# BTLNhung-schematic.net
KiCad netlist of a schematic drawn in Altium Designer
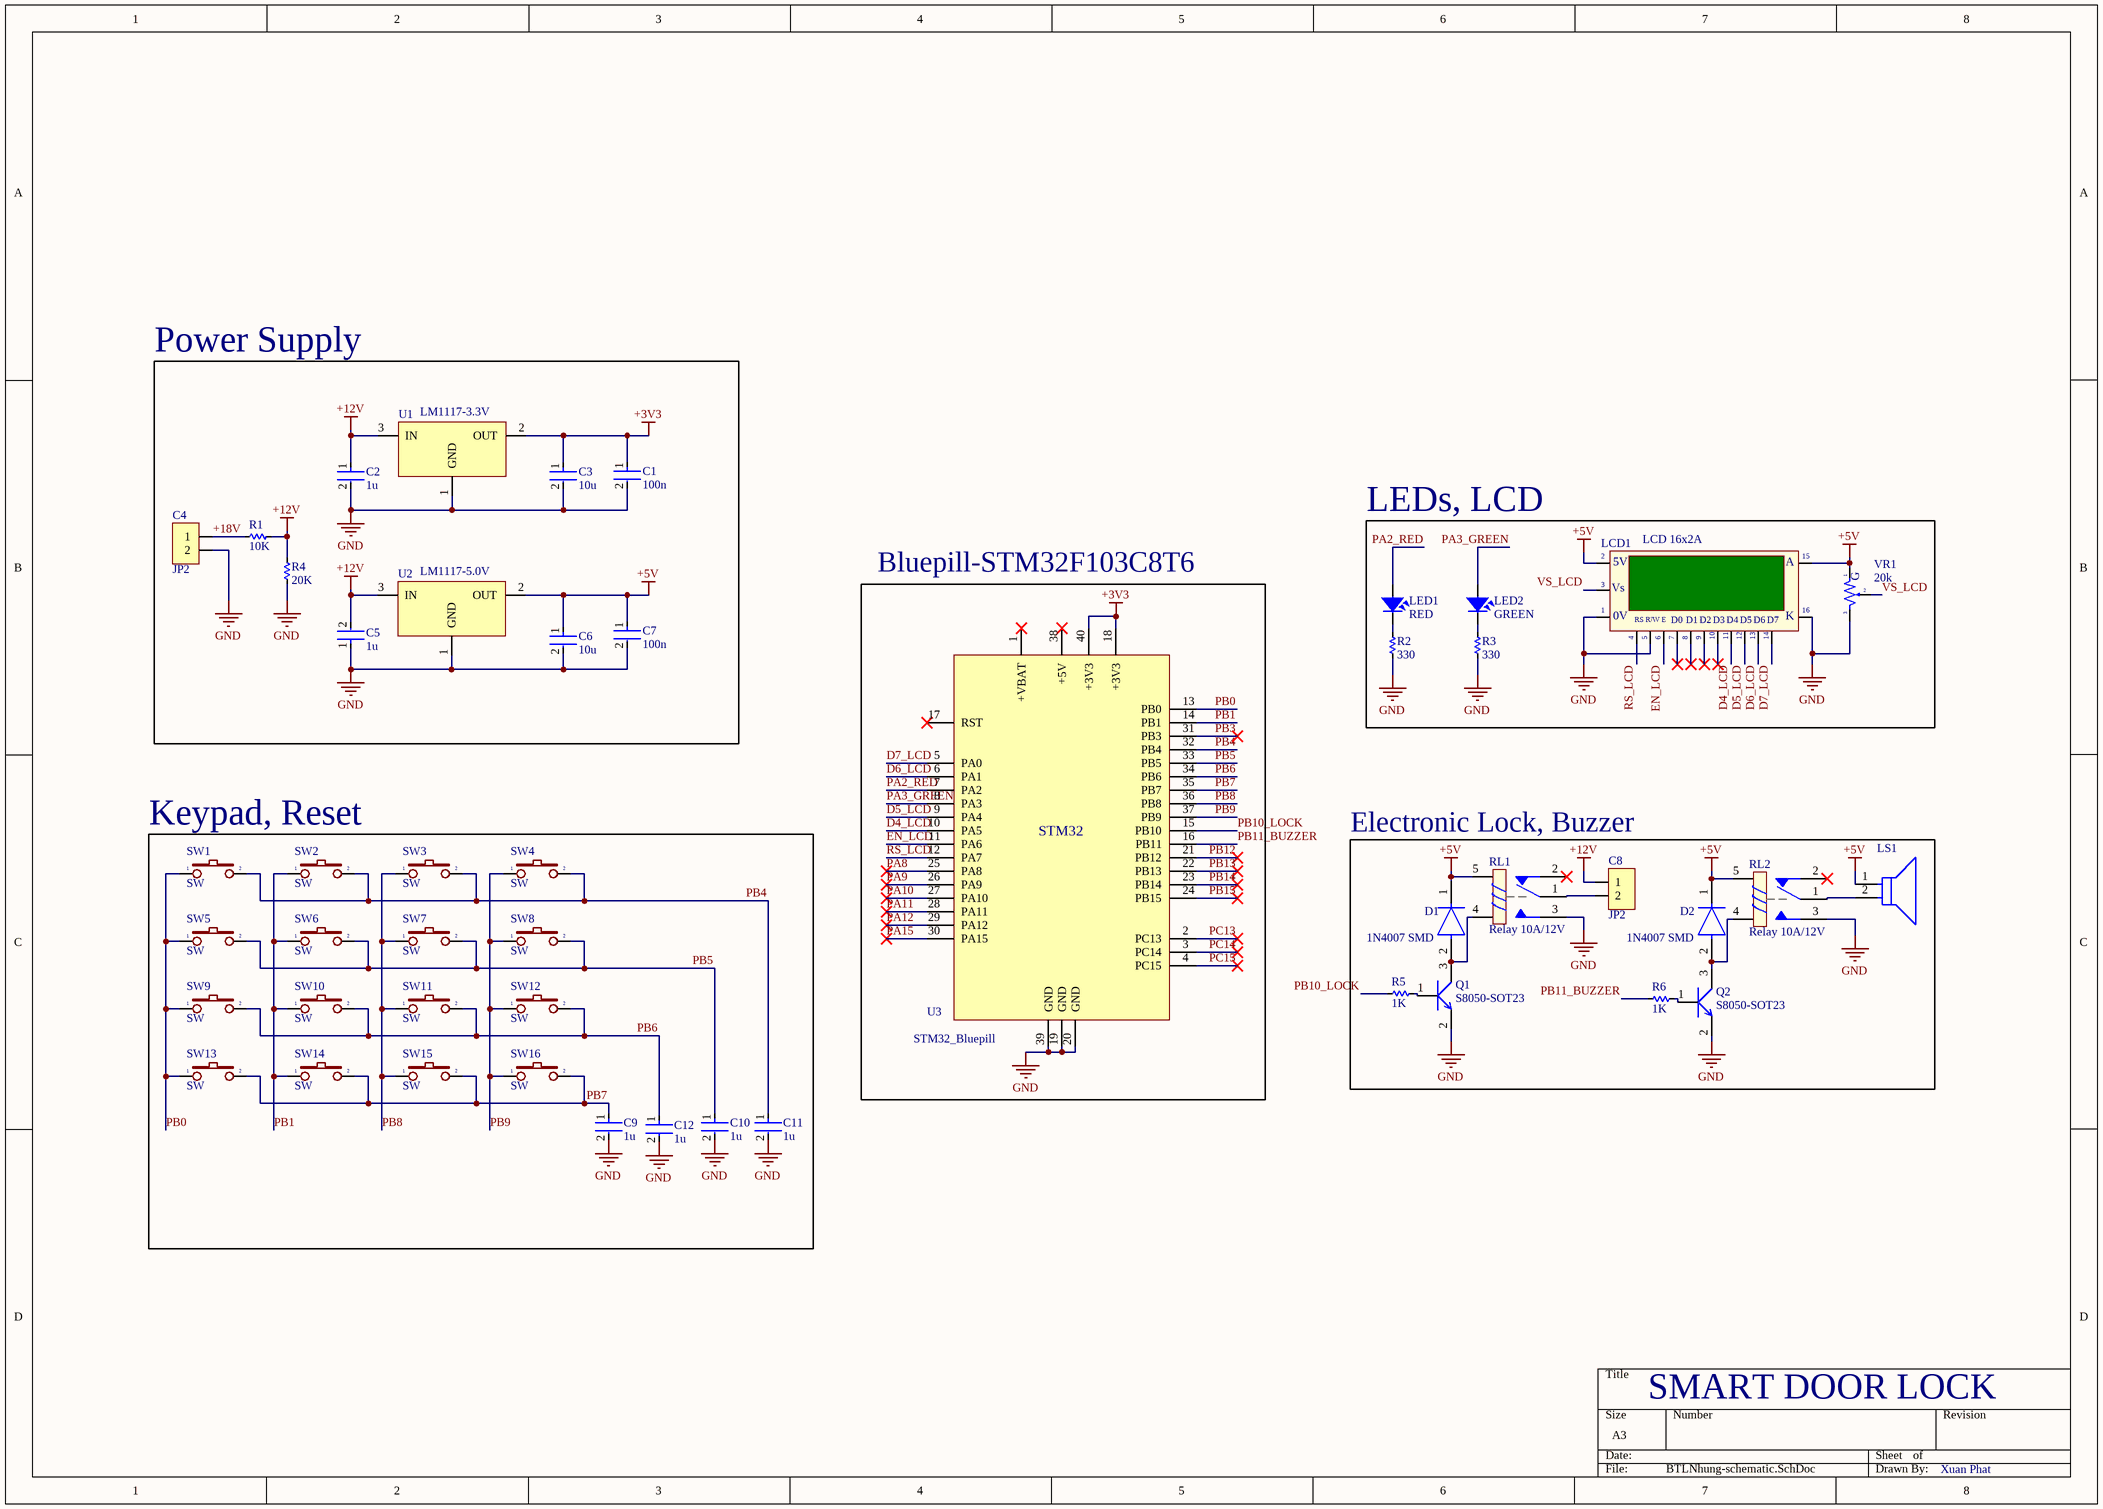
[diagram p0: BTLNhung-schematic.SchDoc]

(export (version "E")
  (design (tool "Eeschema 10.0.6"))
  (components
    (comp (ref "C1")
      (value "100n")
      (footprint "FP-GRM188-0_1-e0_2_0_55-IPC_A")
      (description "Chip Multilayer Ceramic Capacitors for General Purpose, 0603, 10uF, X5R, 15%, 20%, 6.3V")
      (fields (field (name "VOLTAGE") "6.3V") (field (name "TOLERANCE") "20%"))
      (libsource (lib "Altium Content Vault") (part "02cd4be3c70576c341d710602a673aa"))
    )
    (comp (ref "C2")
      (value "1u")
      (footprint "FP-GRM188-0_1-e0_2_0_55-IPC_A")
      (description "Chip Multilayer Ceramic Capacitors for General Purpose, 0603, 10uF, X5R, 15%, 20%, 6.3V")
      (fields (field (name "VOLTAGE") "6.3V") (field (name "TOLERANCE") "20%"))
      (libsource (lib "Altium Content Vault") (part "02cd4be3c70576c341d710602a673aa"))
    )
    (comp (ref "C3")
      (value "10u")
      (footprint "FP-GRM188-0_1-e0_2_0_55-IPC_A")
      (description "Chip Multilayer Ceramic Capacitors for General Purpose, 0603, 10uF, X5R, 15%, 20%, 6.3V")
      (fields (field (name "VOLTAGE") "6.3V") (field (name "TOLERANCE") "20%"))
      (libsource (lib "Altium Content Vault") (part "02cd4be3c70576c341d710602a673aa"))
    )
    (comp (ref "C4")
      (value "JP2")
      (footprint "JP2-D1C")
      (description "WR-PHD 2.54 mm Angled Socket Header")
      (fields
        (field (name "MANUFACTURER") "Würth Elektronik eiSos GmbH")
        (field (name "PARTNO") "613002143121")
        (field (name "CREATED BY") "Karrer Zheng")
      )
      (libsource (lib "") (part "JP2_1"))
    )
    (comp (ref "C5")
      (value "1u")
      (footprint "FP-GRM188-0_1-e0_2_0_55-IPC_A")
      (description "Chip Multilayer Ceramic Capacitors for General Purpose, 0603, 10uF, X5R, 15%, 20%, 6.3V")
      (fields (field (name "VOLTAGE") "6.3V") (field (name "TOLERANCE") "20%"))
      (libsource (lib "Altium Content Vault") (part "02cd4be3c70576c341d710602a673aa"))
    )
    (comp (ref "C6")
      (value "10u")
      (footprint "FP-GRM188-0_1-e0_2_0_55-IPC_A")
      (description "Chip Multilayer Ceramic Capacitors for General Purpose, 0603, 10uF, X5R, 15%, 20%, 6.3V")
      (fields (field (name "VOLTAGE") "6.3V") (field (name "TOLERANCE") "20%"))
      (libsource (lib "Altium Content Vault") (part "02cd4be3c70576c341d710602a673aa"))
    )
    (comp (ref "C7")
      (value "100n")
      (footprint "FP-GRM188-0_1-e0_2_0_55-IPC_A")
      (description "Chip Multilayer Ceramic Capacitors for General Purpose, 0603, 10uF, X5R, 15%, 20%, 6.3V")
      (fields (field (name "VOLTAGE") "6.3V") (field (name "TOLERANCE") "20%"))
      (libsource (lib "Altium Content Vault") (part "02cd4be3c70576c341d710602a673aa"))
    )
    (comp (ref "C8")
      (value "JP2")
      (footprint "JP2-D1C")
      (description "WR-PHD 2.54 mm Angled Socket Header")
      (fields
        (field (name "MANUFACTURER") "Würth Elektronik eiSos GmbH")
        (field (name "PARTNO") "613002143121")
        (field (name "CREATED BY") "Karrer Zheng")
      )
      (libsource (lib "Library") (part "JP2"))
    )
    (comp (ref "C9")
      (value "1u")
      (footprint "FP-GRM188-0_1-e0_2_0_55-IPC_A")
      (description "Chip Multilayer Ceramic Capacitors for General Purpose, 0603, 10uF, X5R, 15%, 20%, 6.3V")
      (fields (field (name "VOLTAGE") "6.3V") (field (name "TOLERANCE") "20%"))
      (libsource (lib "Altium Content Vault") (part "02cd4be3c70576c341d710602a673aa"))
    )
    (comp (ref "C10")
      (value "1u")
      (footprint "FP-GRM188-0_1-e0_2_0_55-IPC_A")
      (description "Chip Multilayer Ceramic Capacitors for General Purpose, 0603, 10uF, X5R, 15%, 20%, 6.3V")
      (fields (field (name "VOLTAGE") "6.3V") (field (name "TOLERANCE") "20%"))
      (libsource (lib "Altium Content Vault") (part "02cd4be3c70576c341d710602a673aa"))
    )
    (comp (ref "C11")
      (value "1u")
      (footprint "FP-GRM188-0_1-e0_2_0_55-IPC_A")
      (description "Chip Multilayer Ceramic Capacitors for General Purpose, 0603, 10uF, X5R, 15%, 20%, 6.3V")
      (fields (field (name "VOLTAGE") "6.3V") (field (name "TOLERANCE") "20%"))
      (libsource (lib "Altium Content Vault") (part "02cd4be3c70576c341d710602a673aa"))
    )
    (comp (ref "C12")
      (value "1u")
      (footprint "FP-GRM188-0_1-e0_2_0_55-IPC_A")
      (description "Chip Multilayer Ceramic Capacitors for General Purpose, 0603, 10uF, X5R, 15%, 20%, 6.3V")
      (fields (field (name "VOLTAGE") "6.3V") (field (name "TOLERANCE") "20%"))
      (libsource (lib "Altium Content Vault") (part "02cd4be3c70576c341d710602a673aa"))
    )
    (comp (ref "D1")
      (value "1N4007 SMD")
      (footprint "FP-1N4007_SMD-IPC_C")
      (description "Rectifier, 1Kv, 1A, Do-214Ac Rohs Compliant: Yes")
      (libsource (lib "Altium Content Vault") (part "d7152d700b627762746794eb795d46e"))
    )
    (comp (ref "D2")
      (value "1N4007 SMD")
      (footprint "FP-1N4007_SMD-IPC_C")
      (description "Rectifier, 1Kv, 1A, Do-214Ac Rohs Compliant: Yes")
      (libsource (lib "Altium Content Vault") (part "d7152d700b627762746794eb795d46e"))
    )
    (comp (ref "LCD1")
      (value "LCD 16x2A")
      (footprint "LCD16X2")
      (description "LCD dipslay 16 char, 2 line")
      (libsource (lib "Library") (part "LCD16x2A"))
    )
    (comp (ref "LED1") (value "RED") (footprint "LED-0805-Red") (libsource (lib "Library") (part "LED SMD")))
    (comp (ref "LED2")
      (value "GREEN")
      (footprint "LED-0805-Green")
      (libsource (lib "Library") (part "LED SMD"))
    )
    (comp (ref "LS1")
      (value "AT-1224-TWT-5V-2-R")
      (footprint "FP-AT-1224-TWT-5V-2-R-MFG")
      (description "BUZZER MAGNETIC 5V 12MM TH")
      (libsource (lib "Altium Content Vault") (part "1973c4b650225fd2ddacaff6b763965"))
    )
    (comp (ref "Q1")
      (value "S8050-SOT23")
      (footprint "SOT95P240X115-3N")
      (description "S8050 J3Y Transistor NPN 25V 0.5A 3 Pins SOT-23")
      (libsource (lib "S8050-SOT23") (part "S8050-SOT23"))
    )
    (comp (ref "Q2")
      (value "S8050-SOT23")
      (footprint "SOT95P240X115-3N")
      (description "S8050 J3Y Transistor NPN 25V 0.5A 3 Pins SOT-23")
      (libsource (lib "S8050-SOT23") (part "S8050-SOT23"))
    )
    (comp (ref "R1")
      (value "10K")
      (footprint "RES-SMD-0805")
      (description "Resistor")
      (fields
        (field (name "MANUFACTURER") "Generic Components")
        (field (name "PUBLISHER") "Altium Hobart Technology Centre")
      )
      (libsource (lib "Library") (part "Res-SMD"))
    )
    (comp (ref "R2")
      (value "330")
      (footprint "RES-SMD-0805")
      (description "Resistor")
      (fields
        (field (name "MANUFACTURER") "Generic Components")
        (field (name "PUBLISHER") "Altium Hobart Technology Centre")
      )
      (libsource (lib "Library") (part "Res-SMD"))
    )
    (comp (ref "R3")
      (value "330")
      (footprint "RES-SMD-0805")
      (description "Resistor")
      (fields
        (field (name "MANUFACTURER") "Generic Components")
        (field (name "PUBLISHER") "Altium Hobart Technology Centre")
      )
      (libsource (lib "Library") (part "Res-SMD"))
    )
    (comp (ref "R4")
      (value "20K")
      (footprint "RES-SMD-0805")
      (description "Resistor")
      (fields
        (field (name "MANUFACTURER") "Generic Components")
        (field (name "PUBLISHER") "Altium Hobart Technology Centre")
      )
      (libsource (lib "Library") (part "Res-SMD"))
    )
    (comp (ref "R5")
      (value "1K")
      (footprint "RES-SMD-0805")
      (description "Resistor")
      (fields
        (field (name "MANUFACTURER") "Generic Components")
        (field (name "PUBLISHER") "Altium Hobart Technology Centre")
      )
      (libsource (lib "Library") (part "Res-SMD"))
    )
    (comp (ref "R6")
      (value "1K")
      (footprint "RES-SMD-0805")
      (description "Resistor")
      (fields
        (field (name "MANUFACTURER") "Generic Components")
        (field (name "PUBLISHER") "Altium Hobart Technology Centre")
      )
      (libsource (lib "Library") (part "Res-SMD"))
    )
    (comp (ref "RL1")
      (value "Relay 10A/12V")
      (footprint "Relay - SRA-05VDC-CL")
      (description "Relay SPDT,10A - 12VDC 5 Pin")
      (libsource (lib "Library") (part "Relay 5"))
    )
    (comp (ref "RL2")
      (value "Relay 10A/12V")
      (footprint "Relay - SRA-05VDC-CL")
      (description "Relay SPDT,10A - 12VDC 5 Pin")
      (libsource (lib "Library") (part "Relay 5"))
    )
    (comp (ref "SW1")
      (value "SW")
      (footprint "SW1-DIP-12x12x8-Black")
      (description "Switch button 2 pin")
      (libsource (lib "Library") (part "SW2"))
    )
    (comp (ref "SW2")
      (value "SW")
      (footprint "SW1-DIP-12x12x8-Black")
      (description "Switch button 2 pin")
      (libsource (lib "Library") (part "SW2"))
    )
    (comp (ref "SW3")
      (value "SW")
      (footprint "SW1-DIP-12x12x8-Black")
      (description "Switch button 2 pin")
      (libsource (lib "Library") (part "SW2"))
    )
    (comp (ref "SW4")
      (value "SW")
      (footprint "SW1-DIP-12x12x8-Black")
      (description "Switch button 2 pin")
      (libsource (lib "Library") (part "SW2"))
    )
    (comp (ref "SW5")
      (value "SW")
      (footprint "SW1-DIP-12x12x8-Black")
      (description "Switch button 2 pin")
      (libsource (lib "Library") (part "SW2"))
    )
    (comp (ref "SW6")
      (value "SW")
      (footprint "SW1-DIP-12x12x8-Black")
      (description "Switch button 2 pin")
      (libsource (lib "Library") (part "SW2"))
    )
    (comp (ref "SW7")
      (value "SW")
      (footprint "SW1-DIP-12x12x8-Black")
      (description "Switch button 2 pin")
      (libsource (lib "Library") (part "SW2"))
    )
    (comp (ref "SW8")
      (value "SW")
      (footprint "SW1-DIP-12x12x8-Black")
      (description "Switch button 2 pin")
      (libsource (lib "Library") (part "SW2"))
    )
    (comp (ref "SW9")
      (value "SW")
      (footprint "SW1-DIP-12x12x8-Black")
      (description "Switch button 2 pin")
      (libsource (lib "Library") (part "SW2"))
    )
    (comp (ref "SW10")
      (value "SW")
      (footprint "SW1-DIP-12x12x8-Black")
      (description "Switch button 2 pin")
      (libsource (lib "Library") (part "SW2"))
    )
    (comp (ref "SW11")
      (value "SW")
      (footprint "SW1-DIP-12x12x8-Black")
      (description "Switch button 2 pin")
      (libsource (lib "Library") (part "SW2"))
    )
    (comp (ref "SW12")
      (value "SW")
      (footprint "SW1-DIP-12x12x8-Black")
      (description "Switch button 2 pin")
      (libsource (lib "Library") (part "SW2"))
    )
    (comp (ref "SW13")
      (value "SW")
      (footprint "SW1-DIP-12x12x8-Black")
      (description "Switch button 2 pin")
      (libsource (lib "Library") (part "SW2"))
    )
    (comp (ref "SW14")
      (value "SW")
      (footprint "SW1-DIP-12x12x8-Black")
      (description "Switch button 2 pin")
      (libsource (lib "Library") (part "SW2"))
    )
    (comp (ref "SW15")
      (value "SW")
      (footprint "SW1-DIP-12x12x8-Black")
      (description "Switch button 2 pin")
      (libsource (lib "Library") (part "SW2"))
    )
    (comp (ref "SW16")
      (value "SW")
      (footprint "SW1-DIP-12x12x8-Black")
      (description "Switch button 2 pin")
      (libsource (lib "Library") (part "SW2"))
    )
    (comp (ref "U1")
      (value "LM1117-3.3V")
      (footprint "SOT223")
      (description "800mA Low-Dropout Linear Regulator")
      (fields (field (name "CREATOR") "Nguyen Ba Bien"))
      (libsource (lib "Library") (part "LM1117"))
    )
    (comp (ref "U2")
      (value "LM1117-5.0V")
      (footprint "SOT223")
      (description "800mA Low-Dropout Linear Regulator")
      (fields (field (name "CREATOR") "Nguyen Ba Bien"))
      (libsource (lib "Library") (part "LM1117"))
    )
    (comp (ref "U3")
      (value "STM32_Bluepill")
      (footprint "STM32F103_BluePill")
      (libsource (lib "Library") (part "STM32_Bluepill"))
    )
    (comp (ref "VR1")
      (value "20k")
      (footprint "VR-S2")
      (description "Var Resistor")
      (libsource (lib "Library") (part "VR-S"))
    )
  )
  (nets
    (net (code "1") (name "+3V3") (class "Default")
      (node (ref "C1") (pin "1") (pinfunction "1_1") (pintype "passive"))
      (node (ref "C3") (pin "1") (pinfunction "1_1") (pintype "passive"))
      (node (ref "U1") (pin "2") (pinfunction "OUT_2") (pintype "passive"))
      (node (ref "U3") (pin "18") (pinfunction "+3V3_18") (pintype "passive"))
      (node (ref "U3") (pin "40") (pinfunction "+3V3_40") (pintype "passive"))
    )
    (net (code "2") (name "+5V") (class "Default")
      (node (ref "C6") (pin "1") (pinfunction "1_1") (pintype "passive"))
      (node (ref "C7") (pin "1") (pinfunction "1_1") (pintype "passive"))
      (node (ref "D1") (pin "1") (pinfunction "C_1") (pintype "passive"))
      (node (ref "D2") (pin "1") (pinfunction "C_1") (pintype "passive"))
      (node (ref "LCD1") (pin "15") (pinfunction "A_15") (pintype "passive"))
      (node (ref "LCD1") (pin "2") (pinfunction "VDD_2") (pintype "passive"))
      (node (ref "LS1") (pin "1") (pinfunction "C_1") (pintype "passive"))
      (node (ref "RL1") (pin "5") (pinfunction "5_5") (pintype "passive"))
      (node (ref "RL2") (pin "5") (pinfunction "5_5") (pintype "passive"))
      (node (ref "U2") (pin "2") (pinfunction "OUT_2") (pintype "passive"))
      (node (ref "VR1") (pin "1") (pinfunction "1_1") (pintype "passive"))
    )
    (net (code "3") (name "+12V") (class "Default")
      (node (ref "C2") (pin "1") (pinfunction "1_1") (pintype "passive"))
      (node (ref "C5") (pin "2") (pinfunction "2_2") (pintype "passive"))
      (node (ref "C8") (pin "1") (pinfunction "1_1") (pintype "passive"))
      (node (ref "R1") (pin "1") (pinfunction "1_1") (pintype "passive"))
      (node (ref "R4") (pin "1") (pinfunction "1_1") (pintype "passive"))
      (node (ref "U1") (pin "3") (pinfunction "IN_3") (pintype "passive"))
      (node (ref "U2") (pin "3") (pinfunction "IN_3") (pintype "passive"))
    )
    (net (code "4") (name "/+18V") (class "Default")
      (node (ref "C4") (pin "1") (pinfunction "1_1") (pintype "passive"))
      (node (ref "R1") (pin "2") (pinfunction "2_2") (pintype "passive"))
    )
    (net (code "5") (name "/D4_LCD") (class "Default")
      (node (ref "LCD1") (pin "11") (pinfunction "D4_11") (pintype "passive"))
      (node (ref "U3") (pin "10") (pinfunction "PA5_10") (pintype "passive"))
    )
    (net (code "6") (name "/D5_LCD") (class "Default")
      (node (ref "LCD1") (pin "12") (pinfunction "D5_12") (pintype "passive"))
      (node (ref "U3") (pin "9") (pinfunction "PA4_9") (pintype "passive"))
    )
    (net (code "7") (name "/D6_LCD") (class "Default")
      (node (ref "LCD1") (pin "13") (pinfunction "D6_13") (pintype "passive"))
      (node (ref "U3") (pin "6") (pinfunction "PA1_6") (pintype "passive"))
    )
    (net (code "8") (name "/D7_LCD") (class "Default")
      (node (ref "LCD1") (pin "14") (pinfunction "D7_14") (pintype "passive"))
      (node (ref "U3") (pin "5") (pinfunction "PA0_5") (pintype "passive"))
    )
    (net (code "9") (name "/EN_LCD") (class "Default")
      (node (ref "LCD1") (pin "6") (pinfunction "~{EN}_6") (pintype "passive"))
      (node (ref "U3") (pin "11") (pinfunction "PA6_11") (pintype "passive"))
    )
    (net (code "10") (name "/PA2_RED") (class "Default")
      (node (ref "LED1") (pin "1") (pinfunction "1_1") (pintype "passive"))
      (node (ref "U3") (pin "7") (pinfunction "PA2_7") (pintype "passive"))
    )
    (net (code "11") (name "/PA3_GREEN") (class "Default")
      (node (ref "LED2") (pin "1") (pinfunction "1_1") (pintype "passive"))
      (node (ref "U3") (pin "8") (pinfunction "PA3_8") (pintype "passive"))
    )
    (net (code "12") (name "/PA8") (class "Default")
      (node (ref "U3") (pin "25") (pinfunction "PA8_25") (pintype "passive+no_connect"))
    )
    (net (code "13") (name "/PA9") (class "Default")
      (node (ref "U3") (pin "26") (pinfunction "PA9_26") (pintype "passive+no_connect"))
    )
    (net (code "14") (name "/PA10") (class "Default")
      (node (ref "U3") (pin "27") (pinfunction "PA10_27") (pintype "passive+no_connect"))
    )
    (net (code "15") (name "/PA11") (class "Default")
      (node (ref "U3") (pin "28") (pinfunction "PA11_28") (pintype "passive+no_connect"))
    )
    (net (code "16") (name "/PA12") (class "Default")
      (node (ref "U3") (pin "29") (pinfunction "PA12_29") (pintype "passive+no_connect"))
    )
    (net (code "17") (name "/PA15") (class "Default")
      (node (ref "U3") (pin "30") (pinfunction "PA15_30") (pintype "passive+no_connect"))
    )
    (net (code "18") (name "/PB0") (class "Default")
      (node (ref "SW1") (pin "1") (pinfunction "1_1") (pintype "passive"))
      (node (ref "SW13") (pin "1") (pinfunction "1_1") (pintype "passive"))
      (node (ref "SW5") (pin "1") (pinfunction "1_1") (pintype "passive"))
      (node (ref "SW9") (pin "1") (pinfunction "1_1") (pintype "passive"))
      (node (ref "U3") (pin "13") (pinfunction "PB0_13") (pintype "passive"))
    )
    (net (code "19") (name "/PB1") (class "Default")
      (node (ref "SW10") (pin "1") (pinfunction "1_1") (pintype "passive"))
      (node (ref "SW14") (pin "1") (pinfunction "1_1") (pintype "passive"))
      (node (ref "SW2") (pin "1") (pinfunction "1_1") (pintype "passive"))
      (node (ref "SW6") (pin "1") (pinfunction "1_1") (pintype "passive"))
      (node (ref "U3") (pin "14") (pinfunction "PB1_14") (pintype "passive"))
    )
    (net (code "20") (name "/PB3") (class "Default")
      (node (ref "U3") (pin "31") (pinfunction "PB3_31") (pintype "passive+no_connect"))
    )
    (net (code "21") (name "/PB4") (class "Default")
      (node (ref "C11") (pin "1") (pinfunction "1_1") (pintype "passive"))
      (node (ref "SW1") (pin "2") (pinfunction "2_2") (pintype "passive"))
      (node (ref "SW2") (pin "2") (pinfunction "2_2") (pintype "passive"))
      (node (ref "SW3") (pin "2") (pinfunction "2_2") (pintype "passive"))
      (node (ref "SW4") (pin "2") (pinfunction "2_2") (pintype "passive"))
      (node (ref "U3") (pin "32") (pinfunction "PB4_32") (pintype "passive"))
    )
    (net (code "22") (name "/PB5") (class "Default")
      (node (ref "C10") (pin "1") (pinfunction "1_1") (pintype "passive"))
      (node (ref "SW5") (pin "2") (pinfunction "2_2") (pintype "passive"))
      (node (ref "SW6") (pin "2") (pinfunction "2_2") (pintype "passive"))
      (node (ref "SW7") (pin "2") (pinfunction "2_2") (pintype "passive"))
      (node (ref "SW8") (pin "2") (pinfunction "2_2") (pintype "passive"))
      (node (ref "U3") (pin "33") (pinfunction "PB5_33") (pintype "passive"))
    )
    (net (code "23") (name "/PB6") (class "Default")
      (node (ref "C12") (pin "1") (pinfunction "1_1") (pintype "passive"))
      (node (ref "SW10") (pin "2") (pinfunction "2_2") (pintype "passive"))
      (node (ref "SW11") (pin "2") (pinfunction "2_2") (pintype "passive"))
      (node (ref "SW12") (pin "2") (pinfunction "2_2") (pintype "passive"))
      (node (ref "SW9") (pin "2") (pinfunction "2_2") (pintype "passive"))
      (node (ref "U3") (pin "34") (pinfunction "PB6_34") (pintype "passive"))
    )
    (net (code "24") (name "/PB7") (class "Default")
      (node (ref "C9") (pin "1") (pinfunction "1_1") (pintype "passive"))
      (node (ref "SW13") (pin "2") (pinfunction "2_2") (pintype "passive"))
      (node (ref "SW14") (pin "2") (pinfunction "2_2") (pintype "passive"))
      (node (ref "SW15") (pin "2") (pinfunction "2_2") (pintype "passive"))
      (node (ref "SW16") (pin "2") (pinfunction "2_2") (pintype "passive"))
      (node (ref "U3") (pin "35") (pinfunction "PB7_35") (pintype "passive"))
    )
    (net (code "25") (name "/PB8") (class "Default")
      (node (ref "SW11") (pin "1") (pinfunction "1_1") (pintype "passive"))
      (node (ref "SW15") (pin "1") (pinfunction "1_1") (pintype "passive"))
      (node (ref "SW3") (pin "1") (pinfunction "1_1") (pintype "passive"))
      (node (ref "SW7") (pin "1") (pinfunction "1_1") (pintype "passive"))
      (node (ref "U3") (pin "36") (pinfunction "PB8_36") (pintype "passive"))
    )
    (net (code "26") (name "/PB9") (class "Default")
      (node (ref "SW12") (pin "1") (pinfunction "1_1") (pintype "passive"))
      (node (ref "SW16") (pin "1") (pinfunction "1_1") (pintype "passive"))
      (node (ref "SW4") (pin "1") (pinfunction "1_1") (pintype "passive"))
      (node (ref "SW8") (pin "1") (pinfunction "1_1") (pintype "passive"))
      (node (ref "U3") (pin "37") (pinfunction "PB9_37") (pintype "passive"))
    )
    (net (code "27") (name "/PB10_LOCK") (class "Default")
      (node (ref "R5") (pin "2") (pinfunction "2_2") (pintype "passive"))
      (node (ref "U3") (pin "15") (pinfunction "PB10_15") (pintype "passive"))
    )
    (net (code "28") (name "/PB11_BUZZER") (class "Default")
      (node (ref "R6") (pin "2") (pinfunction "2_2") (pintype "passive"))
      (node (ref "U3") (pin "16") (pinfunction "PB11_16") (pintype "passive"))
    )
    (net (code "29") (name "/PB12") (class "Default")
      (node (ref "U3") (pin "21") (pinfunction "PB12_21") (pintype "passive+no_connect"))
    )
    (net (code "30") (name "/PB13") (class "Default")
      (node (ref "U3") (pin "22") (pinfunction "PB13_22") (pintype "passive+no_connect"))
    )
    (net (code "31") (name "/PB14") (class "Default")
      (node (ref "U3") (pin "23") (pinfunction "PB14_23") (pintype "passive+no_connect"))
    )
    (net (code "32") (name "/PB15") (class "Default")
      (node (ref "U3") (pin "24") (pinfunction "PB15_24") (pintype "passive+no_connect"))
    )
    (net (code "33") (name "/PC13") (class "Default")
      (node (ref "U3") (pin "2") (pinfunction "PC13_2") (pintype "passive+no_connect"))
    )
    (net (code "34") (name "/PC14") (class "Default")
      (node (ref "U3") (pin "3") (pinfunction "PC14_3") (pintype "passive+no_connect"))
    )
    (net (code "35") (name "/PC15") (class "Default")
      (node (ref "U3") (pin "4") (pinfunction "PC15_4") (pintype "passive+no_connect"))
    )
    (net (code "36") (name "/RS_LCD") (class "Default")
      (node (ref "LCD1") (pin "4") (pinfunction "RS_4") (pintype "passive"))
      (node (ref "U3") (pin "12") (pinfunction "PA7_12") (pintype "passive"))
    )
    (net (code "37") (name "/VS_LCD") (class "Default")
      (node (ref "LCD1") (pin "3") (pinfunction "VEE_3") (pintype "passive"))
      (node (ref "VR1") (pin "2") (pinfunction "2_2") (pintype "passive"))
    )
    (net (code "38") (name "GND") (class "Default")
      (node (ref "C1") (pin "2") (pinfunction "2_2") (pintype "passive"))
      (node (ref "C10") (pin "2") (pinfunction "2_2") (pintype "passive"))
      (node (ref "C11") (pin "2") (pinfunction "2_2") (pintype "passive"))
      (node (ref "C12") (pin "2") (pinfunction "2_2") (pintype "passive"))
      (node (ref "C2") (pin "2") (pinfunction "2_2") (pintype "passive"))
      (node (ref "C3") (pin "2") (pinfunction "2_2") (pintype "passive"))
      (node (ref "C4") (pin "2") (pinfunction "2_2") (pintype "passive"))
      (node (ref "C5") (pin "1") (pinfunction "1_1") (pintype "passive"))
      (node (ref "C6") (pin "2") (pinfunction "2_2") (pintype "passive"))
      (node (ref "C7") (pin "2") (pinfunction "2_2") (pintype "passive"))
      (node (ref "C9") (pin "2") (pinfunction "2_2") (pintype "passive"))
      (node (ref "LCD1") (pin "1") (pinfunction "GND_1") (pintype "passive"))
      (node (ref "LCD1") (pin "16") (pinfunction "K_16") (pintype "passive"))
      (node (ref "LCD1") (pin "5") (pinfunction "R/~{W}_5") (pintype "passive"))
      (node (ref "Q1") (pin "2") (pinfunction "75_2") (pintype "passive"))
      (node (ref "Q2") (pin "2") (pinfunction "75_2") (pintype "passive"))
      (node (ref "R2") (pin "2") (pinfunction "2_2") (pintype "passive"))
      (node (ref "R3") (pin "2") (pinfunction "2_2") (pintype "passive"))
      (node (ref "R4") (pin "2") (pinfunction "2_2") (pintype "passive"))
      (node (ref "RL1") (pin "3") (pinfunction "3_3") (pintype "passive"))
      (node (ref "RL2") (pin "3") (pinfunction "3_3") (pintype "passive"))
      (node (ref "U1") (pin "1") (pinfunction "GND_1") (pintype "passive"))
      (node (ref "U2") (pin "1") (pinfunction "GND_1") (pintype "passive"))
      (node (ref "U3") (pin "19") (pinfunction "GND_19") (pintype "passive"))
      (node (ref "U3") (pin "20") (pinfunction "GND_20") (pintype "passive"))
      (node (ref "U3") (pin "39") (pinfunction "GND_39") (pintype "passive"))
      (node (ref "VR1") (pin "3") (pinfunction "3_3") (pintype "passive"))
    )
    (net (code "39") (name "Net-(C8-Pad2)") (class "Default")
      (node (ref "C8") (pin "2") (pinfunction "2_2") (pintype "passive"))
      (node (ref "RL1") (pin "1") (pinfunction "1_1") (pintype "passive"))
    )
    (net (code "40") (name "Net-(D1-A)") (class "Default")
      (node (ref "D1") (pin "2") (pinfunction "A_2") (pintype "passive"))
      (node (ref "Q1") (pin "3") (pinfunction "77_3") (pintype "passive"))
      (node (ref "RL1") (pin "4") (pinfunction "4_4") (pintype "passive"))
    )
    (net (code "41") (name "Net-(D2-A)") (class "Default")
      (node (ref "D2") (pin "2") (pinfunction "A_2") (pintype "passive"))
      (node (ref "Q2") (pin "3") (pinfunction "77_3") (pintype "passive"))
      (node (ref "RL2") (pin "4") (pinfunction "4_4") (pintype "passive"))
    )
    (net (code "42") (name "Net-(LED1-Pad2)") (class "Default")
      (node (ref "LED1") (pin "2") (pinfunction "2_2") (pintype "passive"))
      (node (ref "R2") (pin "1") (pinfunction "1_1") (pintype "passive"))
    )
    (net (code "43") (name "Net-(LED2-Pad2)") (class "Default")
      (node (ref "LED2") (pin "2") (pinfunction "2_2") (pintype "passive"))
      (node (ref "R3") (pin "1") (pinfunction "1_1") (pintype "passive"))
    )
    (net (code "44") (name "Net-(LS1-A)") (class "Default")
      (node (ref "LS1") (pin "2") (pinfunction "A_2") (pintype "passive"))
      (node (ref "RL2") (pin "1") (pinfunction "1_1") (pintype "passive"))
    )
    (net (code "45") (name "Net-(Q1-Pad1)") (class "Default")
      (node (ref "Q1") (pin "1") (pinfunction "1_1") (pintype "passive"))
      (node (ref "R5") (pin "1") (pinfunction "1_1") (pintype "passive"))
    )
    (net (code "46") (name "Net-(Q2-Pad1)") (class "Default")
      (node (ref "Q2") (pin "1") (pinfunction "1_1") (pintype "passive"))
      (node (ref "R6") (pin "1") (pinfunction "1_1") (pintype "passive"))
    )
    (net (code "47") (name "unconnected-(LCD1-D0-Pad7)") (class "Default")
      (node (ref "LCD1") (pin "7") (pinfunction "D0_7") (pintype "passive+no_connect"))
    )
    (net (code "48") (name "unconnected-(LCD1-D1-Pad8)") (class "Default")
      (node (ref "LCD1") (pin "8") (pinfunction "D1_8") (pintype "passive+no_connect"))
    )
    (net (code "49") (name "unconnected-(LCD1-D2-Pad9)") (class "Default")
      (node (ref "LCD1") (pin "9") (pinfunction "D2_9") (pintype "passive+no_connect"))
    )
    (net (code "50") (name "unconnected-(LCD1-D3-Pad10)") (class "Default")
      (node (ref "LCD1") (pin "10") (pinfunction "D3_10") (pintype "passive+no_connect"))
    )
    (net (code "51") (name "unconnected-(RL1-Pad2)") (class "Default")
      (node (ref "RL1") (pin "2") (pinfunction "2_2") (pintype "passive+no_connect"))
    )
    (net (code "52") (name "unconnected-(RL2-Pad2)") (class "Default")
      (node (ref "RL2") (pin "2") (pinfunction "2_2") (pintype "passive+no_connect"))
    )
    (net (code "53") (name "unconnected-(U3-+5V-Pad38)") (class "Default")
      (node (ref "U3") (pin "38") (pinfunction "+5V_38") (pintype "passive+no_connect"))
    )
    (net (code "54") (name "unconnected-(U3-+VBAT-Pad1)") (class "Default")
      (node (ref "U3") (pin "1") (pinfunction "+VBAT_1") (pintype "passive+no_connect"))
    )
    (net (code "55") (name "unconnected-(U3-RST-Pad17)") (class "Default")
      (node (ref "U3") (pin "17") (pinfunction "RST_17") (pintype "passive+no_connect"))
    )
  )
)
